# WS2812B.net
KiCad netlist of a schematic drawn in Altium Designer
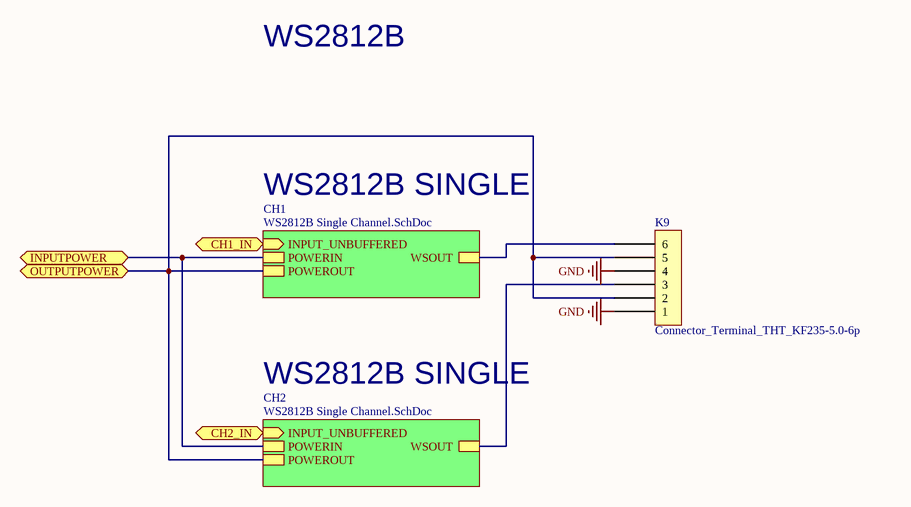
[diagram p0: WS2812B.SchDoc]

(export (version "E")
  (design (tool "Eeschema 10.0.6"))
  (components
    (comp (ref "K9")
      (value "Connector_Terminal_THT_KF235-5.0-6p")
      (footprint "KF235-5.0-6p")
      (libsource (lib "RVA_Altium_Library") (part "Connector_Terminal_THT_KF235-5.0-6p"))
    )
  )
  (nets
    (net (code "4") (name "/OUTPUTPOWER") (class "Default")
      (node (ref "K9") (pin "2") (pinfunction "2_2") (pintype "passive"))
      (node (ref "K9") (pin "5") (pinfunction "5_5") (pintype "passive"))
    )
    (net (code "5") (name "/WSOUT") (class "Default")
      (node (ref "K9") (pin "3") (pinfunction "3_3") (pintype "passive"))
    )
    (net (code "6") (name "/WSOUT_1") (class "Default")
      (node (ref "K9") (pin "6") (pinfunction "6_6") (pintype "passive"))
    )
    (net (code "7") (name "GND") (class "Default")
      (node (ref "K9") (pin "1") (pinfunction "1_1") (pintype "passive"))
      (node (ref "K9") (pin "4") (pinfunction "4_4") (pintype "passive"))
    )
  )
)
